# Pwr.net
KiCad netlist of a schematic drawn in Altium Designer
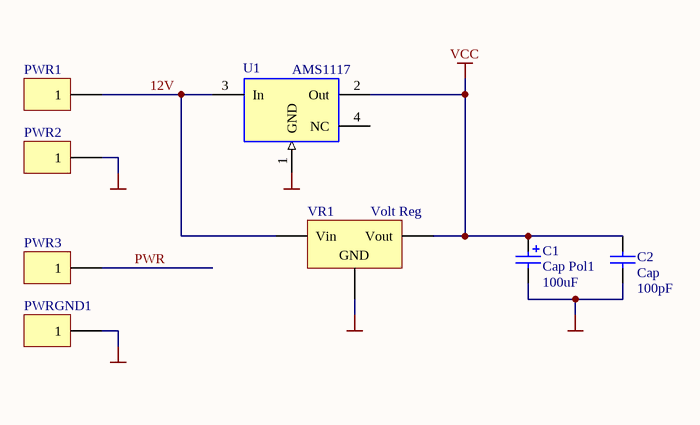
[diagram p0: Pwr.SchDoc]

(export (version "E")
  (design (tool "Eeschema 10.0.6"))
  (components
    (comp (ref "C1")
      (value "Cap Pol1")
      (footprint "RAD-0.3")
      (description "Polarized Capacitor (Radial)")
      (fields (field (name "ALTIUM_VALUE") "100uF") (field (name "PUBLISHER") "Altium Limited"))
      (libsource (lib "Project") (part "Cap Pol1"))
    )
    (comp (ref "C2")
      (value "Cap")
      (footprint "RAD-0.3")
      (description "Capacitor")
      (fields (field (name "ALTIUM_VALUE") "100pF") (field (name "PUBLISHER") "Altium Limited"))
      (libsource (lib "Project") (part "Cap"))
    )
    (comp (ref "PWR1")
      (value "Header TOP 1")
      (footprint "PIN1")
      (description "Header, 1Pin")
      (fields (field (name "PUBLISHER") "Altium Limited"))
      (libsource (lib "Project") (part "Header TOP 1"))
    )
    (comp (ref "PWR2")
      (value "Header TOP 1")
      (footprint "PIN1")
      (description "Header, 1Pin")
      (fields (field (name "PUBLISHER") "Altium Limited"))
      (libsource (lib "Project") (part "Header TOP 1"))
    )
    (comp (ref "PWR3")
      (value "Header TOP 1")
      (footprint "PIN1")
      (description "Header, 1Pin")
      (fields (field (name "PUBLISHER") "Altium Limited"))
      (libsource (lib "Project") (part "Header TOP 1"))
    )
    (comp (ref "PWRGND1")
      (value "Header TOP 1")
      (footprint "PIN1")
      (description "Header, 1Pin")
      (fields (field (name "PUBLISHER") "Altium Limited"))
      (libsource (lib "Project") (part "Header TOP 1"))
    )
    (comp (ref "U1")
      (value "AMS1117")
      (footprint "SOT223_M")
      (description "VOLTAGE REGULATOR")
      (fields (field (name "PUBLISHER") "Altium Limited"))
      (libsource (lib "Project") (part "AMS1117"))
    )
    (comp (ref "VR1")
      (value "Volt Reg")
      (footprint "D2PAK_N")
      (description "Voltage Regulator")
      (fields (field (name "PUBLISHER") "Altium Limited"))
      (libsource (lib "Miscellaneous Devices") (part "Volt Reg"))
    )
  )
  (nets
    (net (code "1") (name "/12V") (class "Default")
      (node (ref "PWR1") (pin "1") (pinfunction "1_1") (pintype "passive"))
      (node (ref "U1") (pin "3") (pinfunction "In_3") (pintype "power_in"))
      (node (ref "VR1") (pin "1") (pinfunction "Vin_1") (pintype "passive"))
    )
    (net (code "2") (name "/PWR") (class "Default")
      (node (ref "PWR3") (pin "1") (pinfunction "1_1") (pintype "passive"))
    )
    (net (code "3") (name "GND") (class "Default")
      (node (ref "C1") (pin "2") (pinfunction "2_2") (pintype "passive"))
      (node (ref "C2") (pin "1") (pinfunction "1_1") (pintype "passive"))
      (node (ref "PWR2") (pin "1") (pinfunction "1_1") (pintype "passive"))
      (node (ref "PWRGND1") (pin "1") (pinfunction "1_1") (pintype "passive"))
      (node (ref "U1") (pin "1") (pinfunction "GND_1") (pintype "input"))
      (node (ref "VR1") (pin "2") (pinfunction "GND_2") (pintype "passive"))
    )
    (net (code "4") (name "VCC") (class "Default")
      (node (ref "C1") (pin "1") (pinfunction "1_1") (pintype "passive"))
      (node (ref "C2") (pin "2") (pinfunction "2_2") (pintype "passive"))
      (node (ref "U1") (pin "2") (pinfunction "Out_2") (pintype "power_in"))
      (node (ref "VR1") (pin "3") (pinfunction "Vout_3") (pintype "passive"))
    )
    (net (code "5") (name "unconnected-(U1-NC-Pad4)") (class "Default")
      (node (ref "U1") (pin "4") (pinfunction "NC_4") (pintype "power_in"))
    )
  )
)
